# SLT3-PAY-1Q2T_P3.net
KiCad netlist of a schematic drawn in Altium Designer
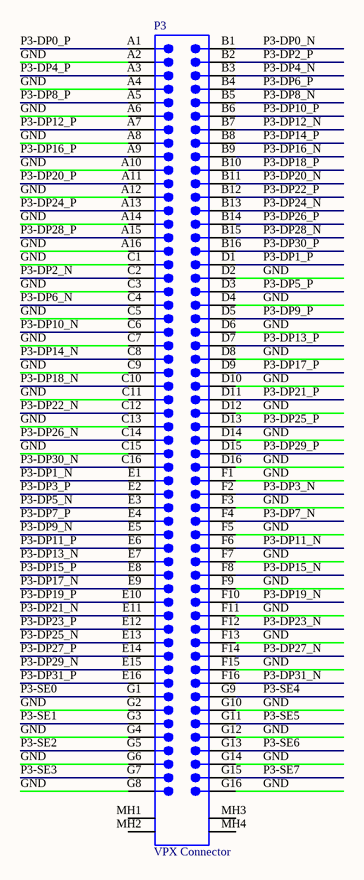
[diagram p0: SLT3-PAY-1Q2T_P3.SchDoc]

(export (version "E")
  (design (tool "Eeschema 10.0.6"))
  (components
    (comp (ref "P3")
      (value "VPX Connector")
      (footprint "BTB1-8-4H112M")
      (description "Ruggedized Board-to-Board Connector, Right Angle, 7-Row, Pitch 1.8mm, 112-Position")
      (fields (field (name "MANUFACTURER") "TE") (field (name "MANUFACTURER PART NUMBER") "2102771-1"))
      (libsource (lib "SVPX") (part "2102771-1"))
    )
  )
  (nets
    (net (code "1") (name "/GND") (class "Default")
      (node (ref "P3") (pin "A10") (pinfunction "A10_A10") (pintype "passive"))
      (node (ref "P3") (pin "A12") (pinfunction "A12_A12") (pintype "passive"))
      (node (ref "P3") (pin "A14") (pinfunction "A14_A14") (pintype "passive"))
      (node (ref "P3") (pin "A16") (pinfunction "A16_A16") (pintype "passive"))
      (node (ref "P3") (pin "A2") (pinfunction "A2_A2") (pintype "passive"))
      (node (ref "P3") (pin "A4") (pinfunction "A4_A4") (pintype "passive"))
      (node (ref "P3") (pin "A6") (pinfunction "A6_A6") (pintype "passive"))
      (node (ref "P3") (pin "A8") (pinfunction "A8_A8") (pintype "passive"))
      (node (ref "P3") (pin "C1") (pinfunction "C1_C1") (pintype "passive"))
      (node (ref "P3") (pin "C11") (pinfunction "C11_C11") (pintype "passive"))
      (node (ref "P3") (pin "C13") (pinfunction "C13_C13") (pintype "passive"))
      (node (ref "P3") (pin "C15") (pinfunction "C15_C15") (pintype "passive"))
      (node (ref "P3") (pin "C3") (pinfunction "C3_C3") (pintype "passive"))
      (node (ref "P3") (pin "C5") (pinfunction "C5_C5") (pintype "passive"))
      (node (ref "P3") (pin "C7") (pinfunction "C7_C7") (pintype "passive"))
      (node (ref "P3") (pin "C9") (pinfunction "C9_C9") (pintype "passive"))
      (node (ref "P3") (pin "D10") (pinfunction "D10_D10") (pintype "passive"))
      (node (ref "P3") (pin "D12") (pinfunction "D12_D12") (pintype "passive"))
      (node (ref "P3") (pin "D14") (pinfunction "D14_D14") (pintype "passive"))
      (node (ref "P3") (pin "D16") (pinfunction "D16_D16") (pintype "passive"))
      (node (ref "P3") (pin "D2") (pinfunction "D2_D2") (pintype "passive"))
      (node (ref "P3") (pin "D4") (pinfunction "D4_D4") (pintype "passive"))
      (node (ref "P3") (pin "D6") (pinfunction "D6_D6") (pintype "passive"))
      (node (ref "P3") (pin "D8") (pinfunction "D8_D8") (pintype "passive"))
      (node (ref "P3") (pin "F1") (pinfunction "F1_F1") (pintype "passive"))
      (node (ref "P3") (pin "F11") (pinfunction "F11_F11") (pintype "passive"))
      (node (ref "P3") (pin "F13") (pinfunction "F13_F13") (pintype "passive"))
      (node (ref "P3") (pin "F15") (pinfunction "F15_F15") (pintype "passive"))
      (node (ref "P3") (pin "F3") (pinfunction "F3_F3") (pintype "passive"))
      (node (ref "P3") (pin "F5") (pinfunction "F5_F5") (pintype "passive"))
      (node (ref "P3") (pin "F7") (pinfunction "F7_F7") (pintype "passive"))
      (node (ref "P3") (pin "F9") (pinfunction "F9_F9") (pintype "passive"))
      (node (ref "P3") (pin "G10") (pinfunction "G10_G10") (pintype "passive"))
      (node (ref "P3") (pin "G12") (pinfunction "G12_G12") (pintype "passive"))
      (node (ref "P3") (pin "G14") (pinfunction "G14_G14") (pintype "passive"))
      (node (ref "P3") (pin "G16") (pinfunction "G16_G16") (pintype "passive"))
      (node (ref "P3") (pin "G2") (pinfunction "G2_G2") (pintype "passive"))
      (node (ref "P3") (pin "G4") (pinfunction "G4_G4") (pintype "passive"))
      (node (ref "P3") (pin "G6") (pinfunction "G6_G6") (pintype "passive"))
      (node (ref "P3") (pin "G8") (pinfunction "G8_G8") (pintype "passive"))
    )
    (net (code "2") (name "/P3-DP0_N") (class "Default")
      (node (ref "P3") (pin "B1") (pinfunction "B1_B1") (pintype "passive"))
    )
    (net (code "3") (name "/P3-DP0_P") (class "Default")
      (node (ref "P3") (pin "A1") (pinfunction "A1_A1") (pintype "passive"))
    )
    (net (code "4") (name "/P3-DP1_N") (class "Default")
      (node (ref "P3") (pin "E1") (pinfunction "E1_E1") (pintype "passive"))
    )
    (net (code "5") (name "/P3-DP1_P") (class "Default")
      (node (ref "P3") (pin "D1") (pinfunction "D1_D1") (pintype "passive"))
    )
    (net (code "6") (name "/P3-DP2_N") (class "Default")
      (node (ref "P3") (pin "C2") (pinfunction "C2_C2") (pintype "passive"))
    )
    (net (code "7") (name "/P3-DP2_P") (class "Default")
      (node (ref "P3") (pin "B2") (pinfunction "B2_B2") (pintype "passive"))
    )
    (net (code "8") (name "/P3-DP3_N") (class "Default")
      (node (ref "P3") (pin "F2") (pinfunction "F2_F2") (pintype "passive"))
    )
    (net (code "9") (name "/P3-DP3_P") (class "Default")
      (node (ref "P3") (pin "E2") (pinfunction "E2_E2") (pintype "passive"))
    )
    (net (code "10") (name "/P3-DP4_N") (class "Default")
      (node (ref "P3") (pin "B3") (pinfunction "B3_B3") (pintype "passive"))
    )
    (net (code "11") (name "/P3-DP4_P") (class "Default")
      (node (ref "P3") (pin "A3") (pinfunction "A3_A3") (pintype "passive"))
    )
    (net (code "12") (name "/P3-DP5_N") (class "Default")
      (node (ref "P3") (pin "E3") (pinfunction "E3_E3") (pintype "passive"))
    )
    (net (code "13") (name "/P3-DP5_P") (class "Default")
      (node (ref "P3") (pin "D3") (pinfunction "D3_D3") (pintype "passive"))
    )
    (net (code "14") (name "/P3-DP6_N") (class "Default")
      (node (ref "P3") (pin "C4") (pinfunction "C4_C4") (pintype "passive"))
    )
    (net (code "15") (name "/P3-DP6_P") (class "Default")
      (node (ref "P3") (pin "B4") (pinfunction "B4_B4") (pintype "passive"))
    )
    (net (code "16") (name "/P3-DP7_N") (class "Default")
      (node (ref "P3") (pin "F4") (pinfunction "F4_F4") (pintype "passive"))
    )
    (net (code "17") (name "/P3-DP7_P") (class "Default")
      (node (ref "P3") (pin "E4") (pinfunction "E4_E4") (pintype "passive"))
    )
    (net (code "18") (name "/P3-DP8_N") (class "Default")
      (node (ref "P3") (pin "B5") (pinfunction "B5_B5") (pintype "passive"))
    )
    (net (code "19") (name "/P3-DP8_P") (class "Default")
      (node (ref "P3") (pin "A5") (pinfunction "A5_A5") (pintype "passive"))
    )
    (net (code "20") (name "/P3-DP9_N") (class "Default")
      (node (ref "P3") (pin "E5") (pinfunction "E5_E5") (pintype "passive"))
    )
    (net (code "21") (name "/P3-DP9_P") (class "Default")
      (node (ref "P3") (pin "D5") (pinfunction "D5_D5") (pintype "passive"))
    )
    (net (code "22") (name "/P3-DP10_N") (class "Default")
      (node (ref "P3") (pin "C6") (pinfunction "C6_C6") (pintype "passive"))
    )
    (net (code "23") (name "/P3-DP10_P") (class "Default")
      (node (ref "P3") (pin "B6") (pinfunction "B6_B6") (pintype "passive"))
    )
    (net (code "24") (name "/P3-DP11_N") (class "Default")
      (node (ref "P3") (pin "F6") (pinfunction "F6_F6") (pintype "passive"))
    )
    (net (code "25") (name "/P3-DP11_P") (class "Default")
      (node (ref "P3") (pin "E6") (pinfunction "E6_E6") (pintype "passive"))
    )
    (net (code "26") (name "/P3-DP12_N") (class "Default")
      (node (ref "P3") (pin "B7") (pinfunction "B7_B7") (pintype "passive"))
    )
    (net (code "27") (name "/P3-DP12_P") (class "Default")
      (node (ref "P3") (pin "A7") (pinfunction "A7_A7") (pintype "passive"))
    )
    (net (code "28") (name "/P3-DP13_N") (class "Default")
      (node (ref "P3") (pin "E7") (pinfunction "E7_E7") (pintype "passive"))
    )
    (net (code "29") (name "/P3-DP13_P") (class "Default")
      (node (ref "P3") (pin "D7") (pinfunction "D7_D7") (pintype "passive"))
    )
    (net (code "30") (name "/P3-DP14_N") (class "Default")
      (node (ref "P3") (pin "C8") (pinfunction "C8_C8") (pintype "passive"))
    )
    (net (code "31") (name "/P3-DP14_P") (class "Default")
      (node (ref "P3") (pin "B8") (pinfunction "B8_B8") (pintype "passive"))
    )
    (net (code "32") (name "/P3-DP15_N") (class "Default")
      (node (ref "P3") (pin "F8") (pinfunction "F8_F8") (pintype "passive"))
    )
    (net (code "33") (name "/P3-DP15_P") (class "Default")
      (node (ref "P3") (pin "E8") (pinfunction "E8_E8") (pintype "passive"))
    )
    (net (code "34") (name "/P3-DP16_N") (class "Default")
      (node (ref "P3") (pin "B9") (pinfunction "B9_B9") (pintype "passive"))
    )
    (net (code "35") (name "/P3-DP16_P") (class "Default")
      (node (ref "P3") (pin "A9") (pinfunction "A9_A9") (pintype "passive"))
    )
    (net (code "36") (name "/P3-DP17_N") (class "Default")
      (node (ref "P3") (pin "E9") (pinfunction "E9_E9") (pintype "passive"))
    )
    (net (code "37") (name "/P3-DP17_P") (class "Default")
      (node (ref "P3") (pin "D9") (pinfunction "D9_D9") (pintype "passive"))
    )
    (net (code "38") (name "/P3-DP18_N") (class "Default")
      (node (ref "P3") (pin "C10") (pinfunction "C10_C10") (pintype "passive"))
    )
    (net (code "39") (name "/P3-DP18_P") (class "Default")
      (node (ref "P3") (pin "B10") (pinfunction "B10_B10") (pintype "passive"))
    )
    (net (code "40") (name "/P3-DP19_N") (class "Default")
      (node (ref "P3") (pin "F10") (pinfunction "F10_F10") (pintype "passive"))
    )
    (net (code "41") (name "/P3-DP19_P") (class "Default")
      (node (ref "P3") (pin "E10") (pinfunction "E10_E10") (pintype "passive"))
    )
    (net (code "42") (name "/P3-DP20_N") (class "Default")
      (node (ref "P3") (pin "B11") (pinfunction "B11_B11") (pintype "passive"))
    )
    (net (code "43") (name "/P3-DP20_P") (class "Default")
      (node (ref "P3") (pin "A11") (pinfunction "A11_A11") (pintype "passive"))
    )
    (net (code "44") (name "/P3-DP21_N") (class "Default")
      (node (ref "P3") (pin "E11") (pinfunction "E11_E11") (pintype "passive"))
    )
    (net (code "45") (name "/P3-DP21_P") (class "Default")
      (node (ref "P3") (pin "D11") (pinfunction "D11_D11") (pintype "passive"))
    )
    (net (code "46") (name "/P3-DP22_N") (class "Default")
      (node (ref "P3") (pin "C12") (pinfunction "C12_C12") (pintype "passive"))
    )
    (net (code "47") (name "/P3-DP22_P") (class "Default")
      (node (ref "P3") (pin "B12") (pinfunction "B12_B12") (pintype "passive"))
    )
    (net (code "48") (name "/P3-DP23_N") (class "Default")
      (node (ref "P3") (pin "F12") (pinfunction "F12_F12") (pintype "passive"))
    )
    (net (code "49") (name "/P3-DP23_P") (class "Default")
      (node (ref "P3") (pin "E12") (pinfunction "E12_E12") (pintype "passive"))
    )
    (net (code "50") (name "/P3-DP24_N") (class "Default")
      (node (ref "P3") (pin "B13") (pinfunction "B13_B13") (pintype "passive"))
    )
    (net (code "51") (name "/P3-DP24_P") (class "Default")
      (node (ref "P3") (pin "A13") (pinfunction "A13_A13") (pintype "passive"))
    )
    (net (code "52") (name "/P3-DP25_N") (class "Default")
      (node (ref "P3") (pin "E13") (pinfunction "E13_E13") (pintype "passive"))
    )
    (net (code "53") (name "/P3-DP25_P") (class "Default")
      (node (ref "P3") (pin "D13") (pinfunction "D13_D13") (pintype "passive"))
    )
    (net (code "54") (name "/P3-DP26_N") (class "Default")
      (node (ref "P3") (pin "C14") (pinfunction "C14_C14") (pintype "passive"))
    )
    (net (code "55") (name "/P3-DP26_P") (class "Default")
      (node (ref "P3") (pin "B14") (pinfunction "B14_B14") (pintype "passive"))
    )
    (net (code "56") (name "/P3-DP27_N") (class "Default")
      (node (ref "P3") (pin "F14") (pinfunction "F14_F14") (pintype "passive"))
    )
    (net (code "57") (name "/P3-DP27_P") (class "Default")
      (node (ref "P3") (pin "E14") (pinfunction "E14_E14") (pintype "passive"))
    )
    (net (code "58") (name "/P3-DP28_N") (class "Default")
      (node (ref "P3") (pin "B15") (pinfunction "B15_B15") (pintype "passive"))
    )
    (net (code "59") (name "/P3-DP28_P") (class "Default")
      (node (ref "P3") (pin "A15") (pinfunction "A15_A15") (pintype "passive"))
    )
    (net (code "60") (name "/P3-DP29_N") (class "Default")
      (node (ref "P3") (pin "E15") (pinfunction "E15_E15") (pintype "passive"))
    )
    (net (code "61") (name "/P3-DP29_P") (class "Default")
      (node (ref "P3") (pin "D15") (pinfunction "D15_D15") (pintype "passive"))
    )
    (net (code "62") (name "/P3-DP30_N") (class "Default")
      (node (ref "P3") (pin "C16") (pinfunction "C16_C16") (pintype "passive"))
    )
    (net (code "63") (name "/P3-DP30_P") (class "Default")
      (node (ref "P3") (pin "B16") (pinfunction "B16_B16") (pintype "passive"))
    )
    (net (code "64") (name "/P3-DP31_N") (class "Default")
      (node (ref "P3") (pin "F16") (pinfunction "F16_F16") (pintype "passive"))
    )
    (net (code "65") (name "/P3-DP31_P") (class "Default")
      (node (ref "P3") (pin "E16") (pinfunction "E16_E16") (pintype "passive"))
    )
    (net (code "66") (name "/P3-SE0") (class "Default")
      (node (ref "P3") (pin "G1") (pinfunction "G1_G1") (pintype "passive"))
    )
    (net (code "67") (name "/P3-SE1") (class "Default")
      (node (ref "P3") (pin "G3") (pinfunction "G3_G3") (pintype "passive"))
    )
    (net (code "68") (name "/P3-SE2") (class "Default")
      (node (ref "P3") (pin "G5") (pinfunction "G5_G5") (pintype "passive"))
    )
    (net (code "69") (name "/P3-SE3") (class "Default")
      (node (ref "P3") (pin "G7") (pinfunction "G7_G7") (pintype "passive"))
    )
    (net (code "70") (name "/P3-SE4") (class "Default")
      (node (ref "P3") (pin "G9") (pinfunction "G9_G9") (pintype "passive"))
    )
    (net (code "71") (name "/P3-SE5") (class "Default")
      (node (ref "P3") (pin "G11") (pinfunction "G11_G11") (pintype "passive"))
    )
    (net (code "72") (name "/P3-SE6") (class "Default")
      (node (ref "P3") (pin "G13") (pinfunction "G13_G13") (pintype "passive"))
    )
    (net (code "73") (name "/P3-SE7") (class "Default")
      (node (ref "P3") (pin "G15") (pinfunction "G15_G15") (pintype "passive"))
    )
    (net (code "74") (name "unconnected-(P3-PadMH1)") (class "Default")
      (node (ref "P3") (pin "MH1") (pinfunction "MH1_MH1") (pintype "passive"))
    )
    (net (code "75") (name "unconnected-(P3-PadMH2)") (class "Default")
      (node (ref "P3") (pin "MH2") (pinfunction "MH2_MH2") (pintype "passive"))
    )
    (net (code "76") (name "unconnected-(P3-PadMH3)") (class "Default")
      (node (ref "P3") (pin "MH3") (pinfunction "MH3_MH3") (pintype "passive"))
    )
    (net (code "77") (name "unconnected-(P3-PadMH4)") (class "Default")
      (node (ref "P3") (pin "MH4") (pinfunction "MH4_MH4") (pintype "passive"))
    )
  )
)
